# Awesome-Shield-0_5.net
KiCad netlist of a schematic drawn in EAGLE
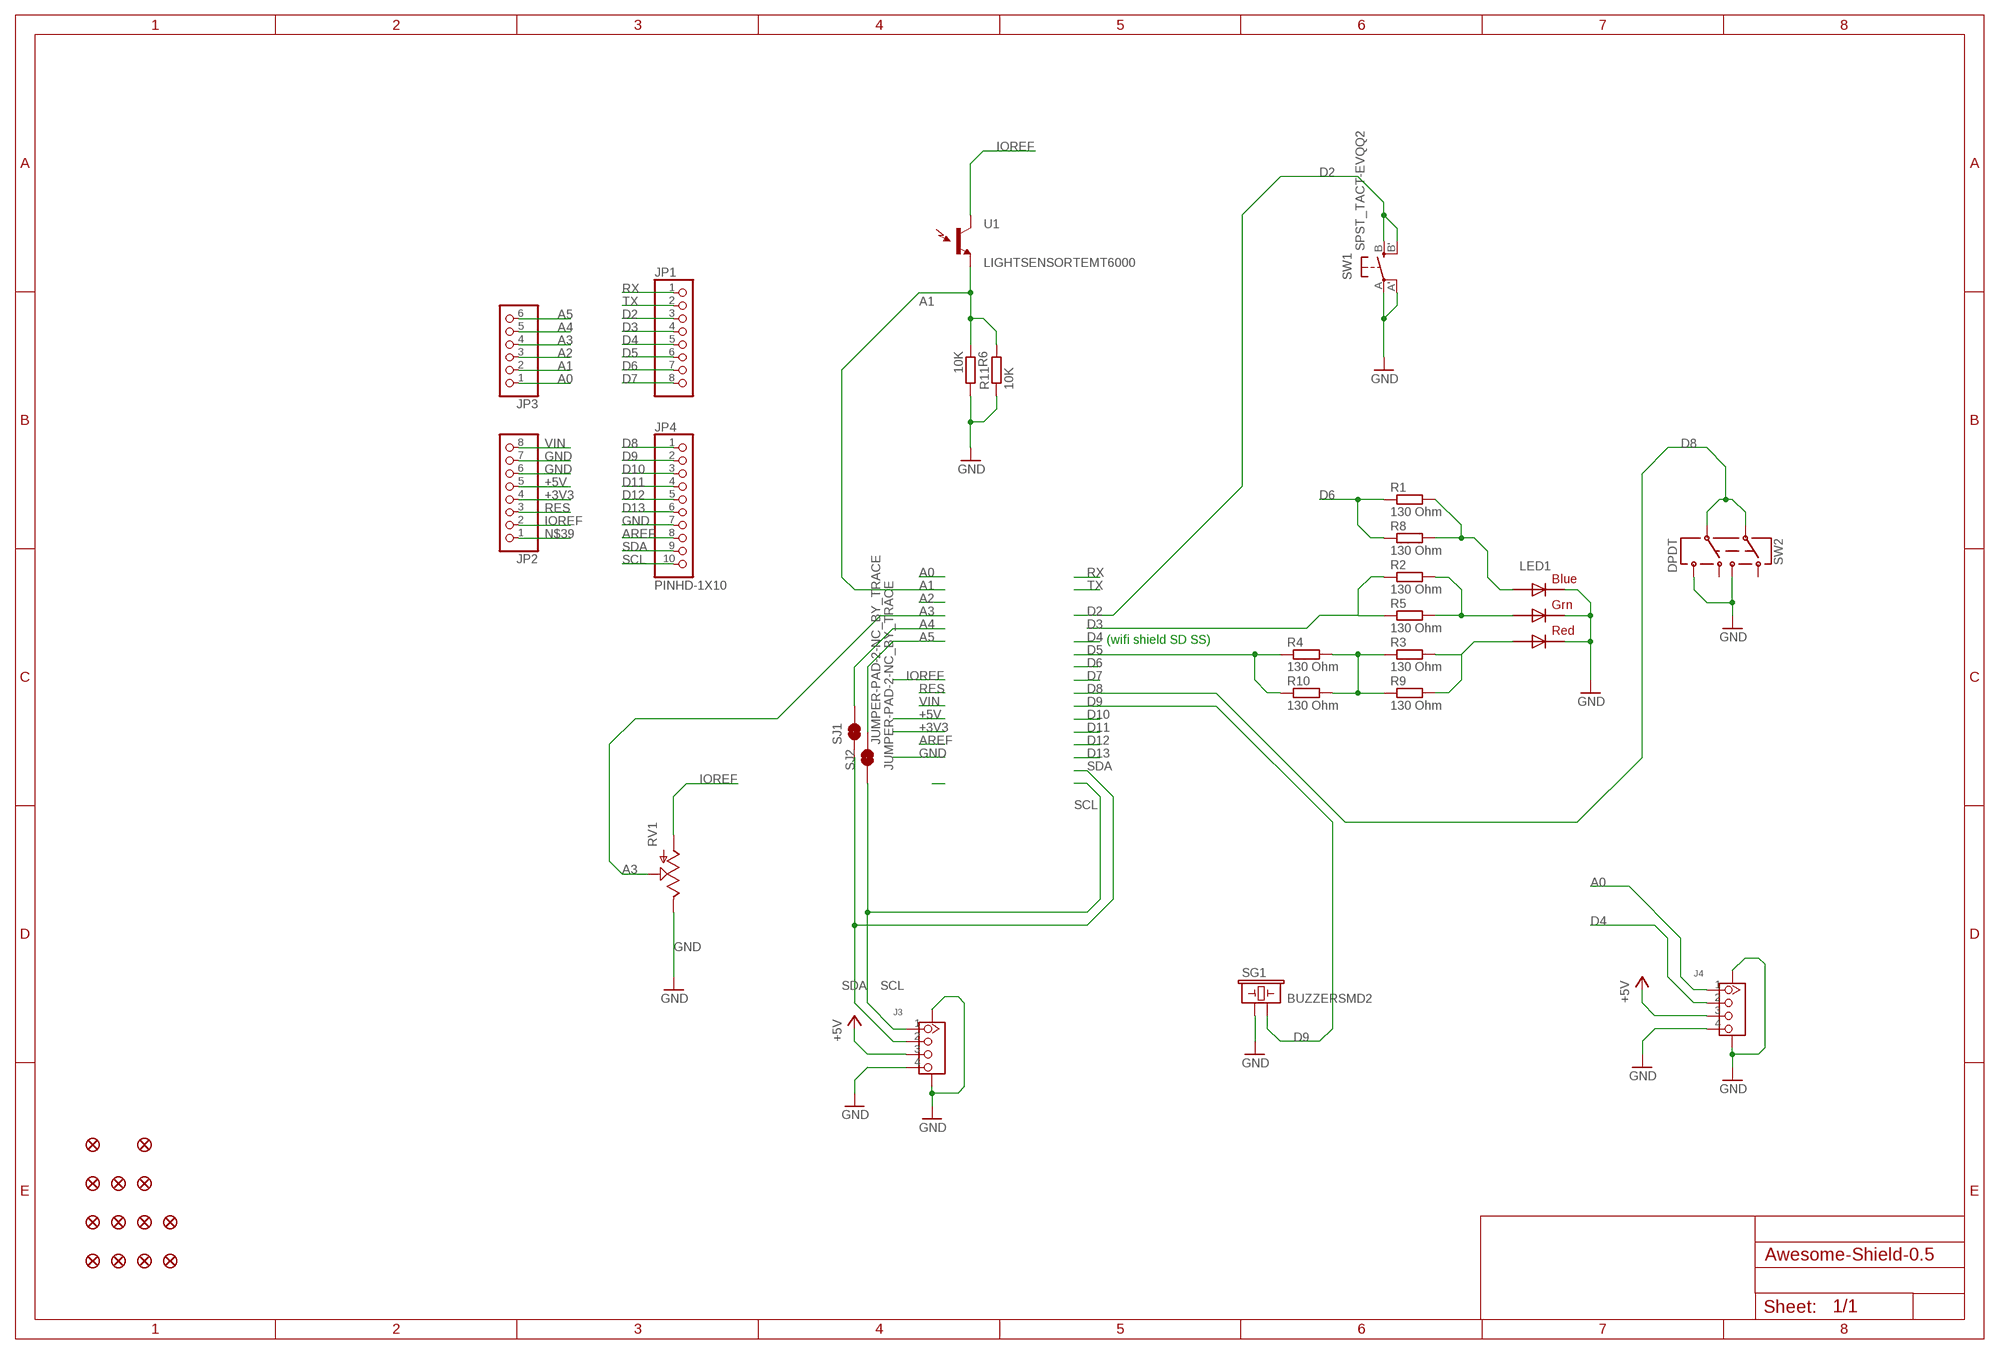
[diagram p0: schematic, sheet 1]

(export (version "E")
  (design (tool "Eeschema 10.0.6"))
  (components
    (comp (ref "FID1")
      (value "FIDUCIAL1X2")
      (footprint "eagle-import:FIDUCIAL-1X2")
      (libsource (lib "eagle-import") (part "FIDUCIAL1X2"))
    )
    (comp (ref "FID2")
      (value "FIDUCIAL1X2")
      (footprint "eagle-import:FIDUCIAL-1X2")
      (libsource (lib "eagle-import") (part "FIDUCIAL1X2"))
    )
    (comp (ref "FID3")
      (value "FIDUCIAL1X2")
      (footprint "eagle-import:FIDUCIAL-1X2")
      (libsource (lib "eagle-import") (part "FIDUCIAL1X2"))
    )
    (comp (ref "FID4")
      (value "FIDUCIAL1X2")
      (footprint "eagle-import:FIDUCIAL-1X2")
      (libsource (lib "eagle-import") (part "FIDUCIAL1X2"))
    )
    (comp (ref "FID5")
      (value "FIDUCIALUFIDUCIAL")
      (footprint "eagle-import:MICRO-FIDUCIAL")
      (libsource (lib "eagle-import") (part "FIDUCIALUFIDUCIAL"))
    )
    (comp (ref "FID6")
      (value "FIDUCIALUFIDUCIAL")
      (footprint "eagle-import:MICRO-FIDUCIAL")
      (libsource (lib "eagle-import") (part "FIDUCIALUFIDUCIAL"))
    )
    (comp (ref "FID7")
      (value "FIDUCIALUFIDUCIAL")
      (footprint "eagle-import:MICRO-FIDUCIAL")
      (libsource (lib "eagle-import") (part "FIDUCIALUFIDUCIAL"))
    )
    (comp (ref "FID8")
      (value "FIDUCIALUFIDUCIAL")
      (footprint "eagle-import:MICRO-FIDUCIAL")
      (libsource (lib "eagle-import") (part "FIDUCIALUFIDUCIAL"))
    )
    (comp (ref "FID9")
      (value "FIDUCIALUFIDUCIAL")
      (footprint "eagle-import:MICRO-FIDUCIAL")
      (libsource (lib "eagle-import") (part "FIDUCIALUFIDUCIAL"))
    )
    (comp (ref "FID10")
      (value "FIDUCIALUFIDUCIAL")
      (footprint "eagle-import:MICRO-FIDUCIAL")
      (libsource (lib "eagle-import") (part "FIDUCIALUFIDUCIAL"))
    )
    (comp (ref "FID11")
      (value "FIDUCIALUFIDUCIAL")
      (footprint "eagle-import:MICRO-FIDUCIAL")
      (libsource (lib "eagle-import") (part "FIDUCIALUFIDUCIAL"))
    )
    (comp (ref "FID13")
      (value "FIDUCIALUFIDUCIAL")
      (footprint "eagle-import:MICRO-FIDUCIAL")
      (libsource (lib "eagle-import") (part "FIDUCIALUFIDUCIAL"))
    )
    (comp (ref "FID15")
      (value "FIDUCIALUFIDUCIAL")
      (footprint "eagle-import:MICRO-FIDUCIAL")
      (libsource (lib "eagle-import") (part "FIDUCIALUFIDUCIAL"))
    )
    (comp (ref "J3")
      (value "GROVE-CONNECTOR-SMD(4+2P-2.0)")
      (footprint "eagle-import:HW4-SMD-2.0")
      (libsource (lib "eagle-import") (part "GROVE-CONNECTOR-SMD(4+2P-2.0)"))
    )
    (comp (ref "J4")
      (value "GROVE-CONNECTOR-SMD(4+2P-2.0)")
      (footprint "eagle-import:HW4-SMD-2.0")
      (libsource (lib "eagle-import") (part "GROVE-CONNECTOR-SMD(4+2P-2.0)"))
    )
    (comp (ref "JP1")
      (value "PINHD-1X8CLEANBIG")
      (footprint "eagle-import:1X08-CLEANBIG")
      (libsource (lib "eagle-import") (part "PINHD-1X8CLEANBIG"))
    )
    (comp (ref "JP2")
      (value "PINHD-1X8CLEANBIG")
      (footprint "eagle-import:1X08-CLEANBIG")
      (libsource (lib "eagle-import") (part "PINHD-1X8CLEANBIG"))
    )
    (comp (ref "JP3")
      (value "PINHD-1X6CLEAN")
      (footprint "eagle-import:1X06-CLEAN")
      (libsource (lib "eagle-import") (part "PINHD-1X6CLEAN"))
    )
    (comp (ref "JP4")
      (value "PINHD-1X10")
      (footprint "eagle-import:1X10-BIG")
      (libsource (lib "eagle-import") (part "PINHD-1X10"))
    )
    (comp (ref "LED1")
      (value "RGBLED5050")
      (footprint "eagle-import:RGBLED5050")
      (libsource (lib "eagle-import") (part "RGBLED5050"))
    )
    (comp (ref "R1")
      (value "130 Ohm")
      (footprint "eagle-import:R1206")
      (libsource (lib "eagle-import") (part "R-EU_R1206"))
    )
    (comp (ref "R2")
      (value "130 Ohm")
      (footprint "eagle-import:R1206")
      (libsource (lib "eagle-import") (part "R-EU_R1206"))
    )
    (comp (ref "R3")
      (value "130 Ohm")
      (footprint "eagle-import:R1206")
      (libsource (lib "eagle-import") (part "R-EU_R1206"))
    )
    (comp (ref "R4")
      (value "130 Ohm")
      (footprint "eagle-import:R1206")
      (libsource (lib "eagle-import") (part "R-EU_R1206"))
    )
    (comp (ref "R5")
      (value "130 Ohm")
      (footprint "eagle-import:R0603")
      (libsource (lib "eagle-import") (part "R-EU_R0603"))
    )
    (comp (ref "R6")
      (value "10K")
      (footprint "eagle-import:R1206")
      (libsource (lib "eagle-import") (part "R-EU_R1206"))
    )
    (comp (ref "R8")
      (value "130 Ohm")
      (footprint "eagle-import:R0603")
      (libsource (lib "eagle-import") (part "R-EU_R0603"))
    )
    (comp (ref "R9")
      (value "130 Ohm")
      (footprint "eagle-import:R0603")
      (libsource (lib "eagle-import") (part "R-EU_R0603"))
    )
    (comp (ref "R10")
      (value "130 Ohm")
      (footprint "eagle-import:R0603")
      (libsource (lib "eagle-import") (part "R-EU_R0603"))
    )
    (comp (ref "R11")
      (value "10K")
      (footprint "eagle-import:R0603")
      (libsource (lib "eagle-import") (part "R-EU_R0603"))
    )
    (comp (ref "RV1")
      (value "POT")
      (footprint "eagle-import:ALPS_POT")
      (libsource (lib "eagle-import") (part "POT"))
    )
    (comp (ref "SG1")
      (value "BUZZERSMD2")
      (footprint "eagle-import:BUZZER-CCV")
      (libsource (lib "eagle-import") (part "BUZZERSMD2"))
    )
    (comp (ref "SJ1")
      (value "JUMPER-PAD-2-NC_BY_TRACE")
      (footprint "eagle-import:PAD-JUMPER-2-NC_BY_TRACE_YES_SILK")
      (libsource (lib "eagle-import") (part "JUMPER-PAD-2-NC_BY_TRACE"))
    )
    (comp (ref "SJ2")
      (value "JUMPER-PAD-2-NC_BY_TRACE")
      (footprint "eagle-import:PAD-JUMPER-2-NC_BY_TRACE_YES_SILK")
      (libsource (lib "eagle-import") (part "JUMPER-PAD-2-NC_BY_TRACE"))
    )
    (comp (ref "SW1")
      (value "SPST_TACT-EVQQ2")
      (footprint "eagle-import:EVQ-Q2")
      (libsource (lib "eagle-import") (part "SPST_TACT-EVQQ2"))
    )
    (comp (ref "SW2")
      (value "DPDT")
      (footprint "eagle-import:AYZ0202")
      (libsource (lib "eagle-import") (part "SWITCH-DPDTAYZ0202"))
    )
    (comp (ref "U1")
      (value "LIGHTSENSORTEMT6000")
      (footprint "eagle-import:TEMT6000-SEN")
      (libsource (lib "eagle-import") (part "LIGHTSENSORTEMT6000"))
    )
  )
  (nets
    (net (code "1") (name "+5V") (class "Default")
      (node (ref "J3") (pin "3") (pinfunction "3_3") (pintype "bidirectional"))
      (node (ref "J4") (pin "3") (pinfunction "3_3") (pintype "bidirectional"))
      (node (ref "JP2") (pin "5") (pinfunction "5_5") (pintype "passive"))
    )
    (net (code "2") (name "/+3V3") (class "Default")
      (node (ref "JP2") (pin "4") (pinfunction "4_4") (pintype "passive"))
    )
    (net (code "3") (name "/A0") (class "Default")
      (node (ref "J4") (pin "1") (pinfunction "1_1") (pintype "bidirectional"))
      (node (ref "JP3") (pin "1") (pinfunction "1_1") (pintype "passive"))
    )
    (net (code "4") (name "/A1") (class "Default")
      (node (ref "JP3") (pin "2") (pinfunction "2_2") (pintype "passive"))
      (node (ref "R11") (pin "2") (pinfunction "2_2") (pintype "passive"))
      (node (ref "R6") (pin "1") (pinfunction "1_1") (pintype "passive"))
      (node (ref "U1") (pin "EMITTER") (pinfunction "E1_EMITTER") (pintype "passive"))
    )
    (net (code "5") (name "/A2") (class "Default")
      (node (ref "JP3") (pin "3") (pinfunction "3_3") (pintype "passive"))
    )
    (net (code "6") (name "/A3") (class "Default")
      (node (ref "JP3") (pin "4") (pinfunction "4_4") (pintype "passive"))
      (node (ref "RV1") (pin "P$2") (pinfunction "S_P$2") (pintype "passive"))
    )
    (net (code "7") (name "/A4") (class "Default")
      (node (ref "JP3") (pin "5") (pinfunction "5_5") (pintype "passive"))
      (node (ref "SJ1") (pin "2") (pinfunction "2_2") (pintype "passive"))
    )
    (net (code "8") (name "/A5") (class "Default")
      (node (ref "JP3") (pin "6") (pinfunction "6_6") (pintype "passive"))
      (node (ref "SJ2") (pin "2") (pinfunction "2_2") (pintype "passive"))
    )
    (net (code "9") (name "/AREF") (class "Default")
      (node (ref "JP4") (pin "8") (pinfunction "8_8") (pintype "passive"))
    )
    (net (code "10") (name "/D2") (class "Default")
      (node (ref "JP1") (pin "3") (pinfunction "3_3") (pintype "passive"))
      (node (ref "SW1") (pin "B") (pinfunction "S_B") (pintype "passive"))
      (node (ref "SW1") (pin "B'") (pinfunction "S1_B'") (pintype "passive"))
    )
    (net (code "11") (name "/D3") (class "Default")
      (node (ref "JP1") (pin "4") (pinfunction "4_4") (pintype "passive"))
      (node (ref "R2") (pin "1") (pinfunction "1_1") (pintype "passive"))
      (node (ref "R5") (pin "1") (pinfunction "1_1") (pintype "passive"))
    )
    (net (code "12") (name "/D4") (class "Default")
      (node (ref "J4") (pin "2") (pinfunction "2_2") (pintype "bidirectional"))
      (node (ref "JP1") (pin "5") (pinfunction "5_5") (pintype "passive"))
    )
    (net (code "13") (name "/D5") (class "Default")
      (node (ref "JP1") (pin "6") (pinfunction "6_6") (pintype "passive"))
      (node (ref "R10") (pin "1") (pinfunction "1_1") (pintype "passive"))
      (node (ref "R4") (pin "1") (pinfunction "1_1") (pintype "passive"))
    )
    (net (code "14") (name "/D6") (class "Default")
      (node (ref "JP1") (pin "7") (pinfunction "7_7") (pintype "passive"))
      (node (ref "R1") (pin "1") (pinfunction "1_1") (pintype "passive"))
      (node (ref "R8") (pin "1") (pinfunction "1_1") (pintype "passive"))
    )
    (net (code "15") (name "/D7") (class "Default")
      (node (ref "JP1") (pin "8") (pinfunction "8_8") (pintype "passive"))
    )
    (net (code "16") (name "/D8") (class "Default")
      (node (ref "JP4") (pin "1") (pinfunction "1_1") (pintype "passive"))
      (node (ref "SW2") (pin "2") (pinfunction "2_2") (pintype "bidirectional"))
      (node (ref "SW2") (pin "5") (pinfunction "5_5") (pintype "bidirectional"))
    )
    (net (code "17") (name "/D9") (class "Default")
      (node (ref "JP4") (pin "2") (pinfunction "2_2") (pintype "passive"))
      (node (ref "SG1") (pin "-") (pinfunction "2_-") (pintype "passive"))
    )
    (net (code "18") (name "/D10") (class "Default")
      (node (ref "JP4") (pin "3") (pinfunction "3_3") (pintype "passive"))
    )
    (net (code "19") (name "/D11") (class "Default")
      (node (ref "JP4") (pin "4") (pinfunction "4_4") (pintype "passive"))
    )
    (net (code "20") (name "/D12") (class "Default")
      (node (ref "JP4") (pin "5") (pinfunction "5_5") (pintype "passive"))
    )
    (net (code "21") (name "/D13") (class "Default")
      (node (ref "JP4") (pin "6") (pinfunction "6_6") (pintype "passive"))
    )
    (net (code "22") (name "/IOREF") (class "Default")
      (node (ref "JP2") (pin "2") (pinfunction "2_2") (pintype "passive"))
      (node (ref "RV1") (pin "P$3") (pinfunction "A_P$3") (pintype "passive"))
      (node (ref "U1") (pin "COLLECTOR") (pinfunction "C1_COLLECTOR") (pintype "passive"))
    )
    (net (code "23") (name "/N$39") (class "Default")
      (node (ref "JP2") (pin "1") (pinfunction "1_1") (pintype "passive"))
    )
    (net (code "24") (name "/RES") (class "Default")
      (node (ref "JP2") (pin "3") (pinfunction "3_3") (pintype "passive"))
    )
    (net (code "25") (name "/RX") (class "Default")
      (node (ref "JP1") (pin "1") (pinfunction "1_1") (pintype "passive"))
    )
    (net (code "26") (name "/SCL") (class "Default")
      (node (ref "J3") (pin "1") (pinfunction "1_1") (pintype "bidirectional"))
      (node (ref "JP4") (pin "10") (pinfunction "10_10") (pintype "passive"))
      (node (ref "SJ2") (pin "1") (pinfunction "1_1") (pintype "passive"))
    )
    (net (code "27") (name "/SDA") (class "Default")
      (node (ref "J3") (pin "2") (pinfunction "2_2") (pintype "bidirectional"))
      (node (ref "JP4") (pin "9") (pinfunction "9_9") (pintype "passive"))
      (node (ref "SJ1") (pin "1") (pinfunction "1_1") (pintype "passive"))
    )
    (net (code "28") (name "/TX") (class "Default")
      (node (ref "JP1") (pin "2") (pinfunction "2_2") (pintype "passive"))
    )
    (net (code "29") (name "/VIN") (class "Default")
      (node (ref "JP2") (pin "8") (pinfunction "8_8") (pintype "passive"))
    )
    (net (code "30") (name "GND") (class "Default")
      (node (ref "J3") (pin "4") (pinfunction "4_4") (pintype "bidirectional"))
      (node (ref "J3") (pin "SS1") (pinfunction "SS1_SS1") (pintype "bidirectional"))
      (node (ref "J3") (pin "SS2") (pinfunction "SS2_SS2") (pintype "bidirectional"))
      (node (ref "J4") (pin "4") (pinfunction "4_4") (pintype "bidirectional"))
      (node (ref "J4") (pin "SS1") (pinfunction "SS1_SS1") (pintype "bidirectional"))
      (node (ref "J4") (pin "SS2") (pinfunction "SS2_SS2") (pintype "bidirectional"))
      (node (ref "JP2") (pin "6") (pinfunction "6_6") (pintype "passive"))
      (node (ref "JP2") (pin "7") (pinfunction "7_7") (pintype "passive"))
      (node (ref "JP4") (pin "7") (pinfunction "7_7") (pintype "passive"))
      (node (ref "LED1") (pin "4") (pinfunction "BLUE_C_4") (pintype "bidirectional"))
      (node (ref "LED1") (pin "5") (pinfunction "RED_C_5") (pintype "bidirectional"))
      (node (ref "LED1") (pin "6") (pinfunction "GREEN_C_6") (pintype "bidirectional"))
      (node (ref "R11") (pin "1") (pinfunction "1_1") (pintype "passive"))
      (node (ref "R6") (pin "2") (pinfunction "2_2") (pintype "passive"))
      (node (ref "RV1") (pin "P$1") (pinfunction "E_P$1") (pintype "passive"))
      (node (ref "SG1") (pin "+") (pinfunction "1_+") (pintype "passive"))
      (node (ref "SW1") (pin "A") (pinfunction "P_A") (pintype "passive"))
      (node (ref "SW1") (pin "A'") (pinfunction "P1_A'") (pintype "passive"))
      (node (ref "SW2") (pin "3") (pinfunction "3_3") (pintype "bidirectional"))
      (node (ref "SW2") (pin "6") (pinfunction "6_6") (pintype "bidirectional"))
    )
    (net (code "31") (name "Net-(LED1-BLUE_A)") (class "Default")
      (node (ref "LED1") (pin "3") (pinfunction "BLUE_A_3") (pintype "bidirectional"))
      (node (ref "R1") (pin "2") (pinfunction "2_2") (pintype "passive"))
      (node (ref "R8") (pin "2") (pinfunction "2_2") (pintype "passive"))
    )
    (net (code "32") (name "Net-(LED1-GREEN_A)") (class "Default")
      (node (ref "LED1") (pin "1") (pinfunction "GREEN_A_1") (pintype "bidirectional"))
      (node (ref "R2") (pin "2") (pinfunction "2_2") (pintype "passive"))
      (node (ref "R5") (pin "2") (pinfunction "2_2") (pintype "passive"))
    )
    (net (code "33") (name "Net-(LED1-RED_A)") (class "Default")
      (node (ref "LED1") (pin "2") (pinfunction "RED_A_2") (pintype "bidirectional"))
      (node (ref "R3") (pin "2") (pinfunction "2_2") (pintype "passive"))
      (node (ref "R9") (pin "2") (pinfunction "2_2") (pintype "passive"))
    )
    (net (code "34") (name "Net-(R10-Pad2)") (class "Default")
      (node (ref "R10") (pin "2") (pinfunction "2_2") (pintype "passive"))
      (node (ref "R3") (pin "1") (pinfunction "1_1") (pintype "passive"))
      (node (ref "R4") (pin "2") (pinfunction "2_2") (pintype "passive"))
      (node (ref "R9") (pin "1") (pinfunction "1_1") (pintype "passive"))
    )
    (net (code "35") (name "unconnected-(SW2-Pad1)") (class "Default")
      (node (ref "SW2") (pin "1") (pinfunction "1_1") (pintype "bidirectional"))
    )
    (net (code "36") (name "unconnected-(SW2-Pad4)") (class "Default")
      (node (ref "SW2") (pin "4") (pinfunction "4_4") (pintype "bidirectional"))
    )
  )
)
